# 04_CH340.net
KiCad netlist of a schematic drawn in Altium Designer
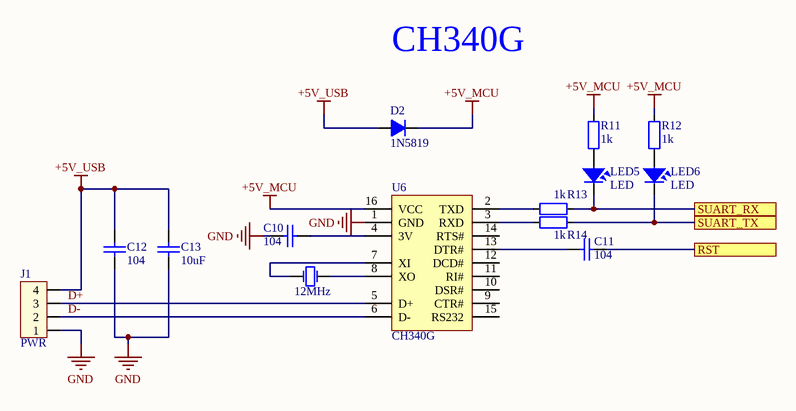
[diagram p0: [04] CH340.SchDoc]

(export (version "E")
  (design (tool "Eeschema 10.0.6"))
  (components
    (comp (ref "C10")
      (value "104")
      (footprint "CAP_0805")
      (description "Capacitor")
      (fields (field (name "PUBLISHER") "Altium Limited"))
      (libsource (lib "My Library") (part "CapSMD"))
    )
    (comp (ref "C11")
      (value "104")
      (footprint "CAP_0805")
      (description "Capacitor")
      (fields (field (name "PUBLISHER") "Altium Limited"))
      (libsource (lib "My Library") (part "CapSMD"))
    )
    (comp (ref "C12")
      (value "104")
      (footprint "CAP_0805")
      (description "Capacitor")
      (fields (field (name "PUBLISHER") "Altium Limited"))
      (libsource (lib "My Library") (part "CapSMD"))
    )
    (comp (ref "C13")
      (value "10uF")
      (footprint "CAP_0805")
      (description "Capacitor")
      (fields (field (name "PUBLISHER") "Altium Limited"))
      (libsource (lib "My Library") (part "CapSMD"))
    )
    (comp (ref "D2")
      (value "1N5819")
      (footprint "DO-214AB SMA")
      (description "Diode 1A")
      (libsource (lib "GPS_Traking_V1_1") (part "D1A_1"))
    )
    (comp (ref "J1")
      (value "PWR")
      (footprint "HED4B")
      (description "Header 4 (Green)")
      (libsource (lib "GPS_Traking_V1_1") (part "Hed4"))
    )
    (comp (ref "LED5")
      (value "LED")
      (footprint "LED-0805-Green")
      (description "LED Single colour Green and Red")
      (libsource (lib "My Library") (part "LED"))
    )
    (comp (ref "LED6")
      (value "LED")
      (footprint "LED-0805-Green")
      (description "LED Single colour Green and Red")
      (libsource (lib "My Library") (part "LED"))
    )
    (comp (ref "R11")
      (value "1k")
      (footprint "RES-SMD-0805")
      (description "Resistor")
      (fields
        (field (name "MANUFACTURER") "Generic Components")
        (field (name "PUBLISHER") "Altium Hobart Technology Centre")
      )
      (libsource (lib "My Library") (part "Resistor - SMD"))
    )
    (comp (ref "R12")
      (value "1k")
      (footprint "RES-SMD-0805")
      (description "Resistor")
      (fields
        (field (name "MANUFACTURER") "Generic Components")
        (field (name "PUBLISHER") "Altium Hobart Technology Centre")
      )
      (libsource (lib "My Library") (part "Resistor - SMD"))
    )
    (comp (ref "R13")
      (value "1k")
      (footprint "RES-SMD-0805")
      (description "Resistor")
      (fields
        (field (name "MANUFACTURER") "Generic Components")
        (field (name "PUBLISHER") "Altium Hobart Technology Centre")
      )
      (libsource (lib "My Library") (part "Resistor - SMD"))
    )
    (comp (ref "R14")
      (value "1k")
      (footprint "RES-SMD-0805")
      (description "Resistor")
      (fields
        (field (name "MANUFACTURER") "Generic Components")
        (field (name "PUBLISHER") "Altium Hobart Technology Centre")
      )
      (libsource (lib "My Library") (part "Resistor - SMD"))
    )
    (comp (ref "U6")
      (value "CH340G")
      (footprint "SO16")
      (description "High and Low Side Driver")
      (fields (field (name "PUBLISHER") "Altium Limited"))
      (libsource (lib "My Library") (part "CH340G"))
    )
    (comp (ref "Y2")
      (value "12MHz")
      (footprint "XTAL 5032 SMD")
      (description "Crystal Oscillator")
      (fields (field (name "PUBLISHER") "Altium Limited"))
      (libsource (lib "My Library") (part "XTAL"))
    )
  )
  (nets
    (net (code "1") (name "+5V_MCU") (class "Default")
      (node (ref "D2") (pin "2") (pinfunction "K_2") (pintype "passive"))
      (node (ref "R11") (pin "2") (pinfunction "2_2") (pintype "passive"))
      (node (ref "R12") (pin "2") (pinfunction "2_2") (pintype "passive"))
      (node (ref "U6") (pin "16") (pinfunction "VCC_16") (pintype "passive"))
    )
    (net (code "2") (name "+5V_USB") (class "Default")
      (node (ref "C12") (pin "2") (pinfunction "2_2") (pintype "passive"))
      (node (ref "C13") (pin "2") (pinfunction "2_2") (pintype "passive"))
      (node (ref "D2") (pin "1") (pinfunction "A_1") (pintype "passive"))
      (node (ref "J1") (pin "4") (pinfunction "4_4") (pintype "passive"))
    )
    (net (code "3") (name "/D+") (class "Default")
      (node (ref "J1") (pin "3") (pinfunction "3_3") (pintype "passive"))
      (node (ref "U6") (pin "5") (pinfunction "D+_5") (pintype "passive"))
    )
    (net (code "4") (name "/D-") (class "Default")
      (node (ref "J1") (pin "2") (pinfunction "2_2") (pintype "passive"))
      (node (ref "U6") (pin "6") (pinfunction "D-_6") (pintype "passive"))
    )
    (net (code "5") (name "/RST") (class "Default")
      (node (ref "C11") (pin "2") (pinfunction "2_2") (pintype "passive"))
    )
    (net (code "6") (name "/SUART_RX") (class "Default")
      (node (ref "LED5") (pin "2") (pinfunction "2_2") (pintype "passive"))
      (node (ref "R13") (pin "2") (pinfunction "2_2") (pintype "passive"))
    )
    (net (code "7") (name "/SUART_TX") (class "Default")
      (node (ref "LED6") (pin "2") (pinfunction "2_2") (pintype "passive"))
      (node (ref "R14") (pin "2") (pinfunction "2_2") (pintype "passive"))
    )
    (net (code "8") (name "GND") (class "Default")
      (node (ref "C10") (pin "1") (pinfunction "1_1") (pintype "passive"))
      (node (ref "C12") (pin "1") (pinfunction "1_1") (pintype "passive"))
      (node (ref "C13") (pin "1") (pinfunction "1_1") (pintype "passive"))
      (node (ref "J1") (pin "1") (pinfunction "1_1") (pintype "passive"))
      (node (ref "U6") (pin "1") (pinfunction "GND_1") (pintype "passive"))
    )
    (net (code "9") (name "Net-(LED5-Pad1)") (class "Default")
      (node (ref "LED5") (pin "1") (pinfunction "1_1") (pintype "passive"))
      (node (ref "R11") (pin "1") (pinfunction "1_1") (pintype "passive"))
    )
    (net (code "10") (name "Net-(LED6-Pad1)") (class "Default")
      (node (ref "LED6") (pin "1") (pinfunction "1_1") (pintype "passive"))
      (node (ref "R12") (pin "1") (pinfunction "1_1") (pintype "passive"))
    )
    (net (code "11") (name "Net-(U6-3V)") (class "Default")
      (node (ref "C10") (pin "2") (pinfunction "2_2") (pintype "passive"))
      (node (ref "U6") (pin "4") (pinfunction "3V_4") (pintype "passive"))
    )
    (net (code "12") (name "Net-(U6-DTR#)") (class "Default")
      (node (ref "C11") (pin "1") (pinfunction "1_1") (pintype "passive"))
      (node (ref "U6") (pin "13") (pinfunction "DTR#_13") (pintype "passive"))
    )
    (net (code "13") (name "Net-(U6-RXD)") (class "Default")
      (node (ref "R14") (pin "1") (pinfunction "1_1") (pintype "passive"))
      (node (ref "U6") (pin "3") (pinfunction "RXD_3") (pintype "passive"))
    )
    (net (code "14") (name "Net-(U6-TXD)") (class "Default")
      (node (ref "R13") (pin "1") (pinfunction "1_1") (pintype "passive"))
      (node (ref "U6") (pin "2") (pinfunction "TXD_2") (pintype "passive"))
    )
    (net (code "15") (name "Net-(U6-XI)") (class "Default")
      (node (ref "U6") (pin "7") (pinfunction "XI_7") (pintype "passive"))
      (node (ref "Y2") (pin "1") (pinfunction "OSC1_1") (pintype "passive"))
    )
    (net (code "16") (name "Net-(U6-XO)") (class "Default")
      (node (ref "U6") (pin "8") (pinfunction "XO_8") (pintype "passive"))
      (node (ref "Y2") (pin "2") (pinfunction "OSC2_2") (pintype "passive"))
    )
    (net (code "17") (name "unconnected-(U6-CTR#-Pad9)") (class "Default")
      (node (ref "U6") (pin "9") (pinfunction "CTR#_9") (pintype "passive"))
    )
    (net (code "18") (name "unconnected-(U6-DCD#-Pad12)") (class "Default")
      (node (ref "U6") (pin "12") (pinfunction "DCD#_12") (pintype "passive"))
    )
    (net (code "19") (name "unconnected-(U6-DSR#-Pad10)") (class "Default")
      (node (ref "U6") (pin "10") (pinfunction "DSR#_10") (pintype "passive"))
    )
    (net (code "20") (name "unconnected-(U6-RI#-Pad11)") (class "Default")
      (node (ref "U6") (pin "11") (pinfunction "RI#_11") (pintype "passive"))
    )
    (net (code "21") (name "unconnected-(U6-RS232-Pad15)") (class "Default")
      (node (ref "U6") (pin "15") (pinfunction "RS232_15") (pintype "passive"))
    )
    (net (code "22") (name "unconnected-(U6-RTS#-Pad14)") (class "Default")
      (node (ref "U6") (pin "14") (pinfunction "RTS#_14") (pintype "passive"))
    )
  )
)
